# nixie-tube-clock_tube.net
KiCad netlist of a schematic drawn in EAGLE
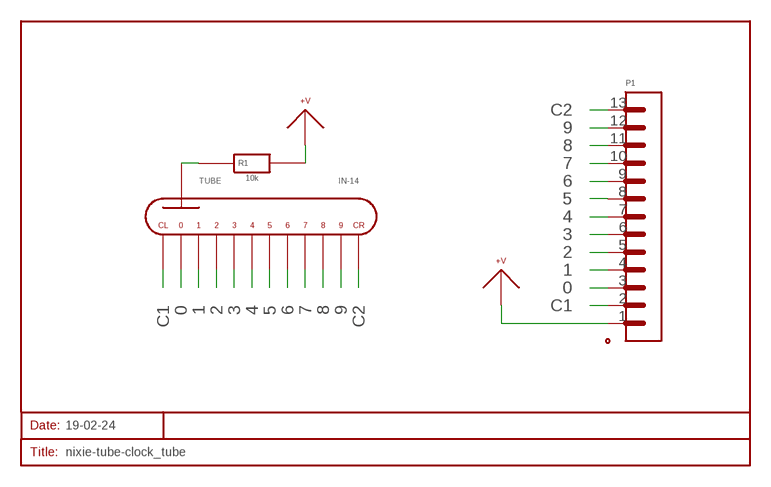
[diagram p0: schematic, sheet 1]

(export (version "E")
  (design (tool "Eeschema 10.0.6"))
  (components
    (comp (ref "P1")
      (value "PORT_13-PIN_HEADER")
      (footprint "eagle-import:HEADER_13-PIN")
      (libsource (lib "eagle-import") (part "PORT_13-PIN_HEADER"))
    )
    (comp (ref "R1")
      (value "10k")
      (footprint "eagle-import:RESISTOR_10.16MM")
      (libsource (lib "eagle-import") (part "RESISTOR"))
    )
    (comp (ref "SCHEMATIC1")
      (value "19-02-24")
      (footprint "eagle-import:SHEET")
      (libsource (lib "eagle-import") (part "SHEET"))
    )
    (comp (ref "TUBE")
      (value "IN-14")
      (footprint "eagle-import:NIXIE-TUBE_IN-14")
      (libsource (lib "eagle-import") (part "NIXIE-TUBE_IN-14_TUBE"))
    )
  )
  (nets
    (net (code "1") (name "+V") (class "Default")
      (node (ref "P1") (pin "1") (pinfunction "1_1") (pintype "bidirectional"))
      (node (ref "R1") (pin "2") (pinfunction "2_2") (pintype "bidirectional"))
    )
    (net (code "2") (name "/0") (class "Default")
      (node (ref "P1") (pin "3") (pinfunction "3_3") (pintype "bidirectional"))
      (node (ref "TUBE") (pin "0") (pinfunction "0_0") (pintype "bidirectional"))
    )
    (net (code "3") (name "/1") (class "Default")
      (node (ref "P1") (pin "4") (pinfunction "4_4") (pintype "bidirectional"))
      (node (ref "TUBE") (pin "1") (pinfunction "1_1") (pintype "bidirectional"))
    )
    (net (code "4") (name "/2") (class "Default")
      (node (ref "P1") (pin "5") (pinfunction "5_5") (pintype "bidirectional"))
      (node (ref "TUBE") (pin "2") (pinfunction "2_2") (pintype "bidirectional"))
    )
    (net (code "5") (name "/3") (class "Default")
      (node (ref "P1") (pin "6") (pinfunction "6_6") (pintype "bidirectional"))
      (node (ref "TUBE") (pin "3") (pinfunction "3_3") (pintype "bidirectional"))
    )
    (net (code "6") (name "/4") (class "Default")
      (node (ref "P1") (pin "7") (pinfunction "7_7") (pintype "bidirectional"))
      (node (ref "TUBE") (pin "4") (pinfunction "4_4") (pintype "bidirectional"))
    )
    (net (code "7") (name "/5") (class "Default")
      (node (ref "P1") (pin "8") (pinfunction "8_8") (pintype "bidirectional"))
      (node (ref "TUBE") (pin "5") (pinfunction "5_5") (pintype "bidirectional"))
    )
    (net (code "8") (name "/6") (class "Default")
      (node (ref "P1") (pin "9") (pinfunction "9_9") (pintype "bidirectional"))
      (node (ref "TUBE") (pin "6") (pinfunction "6_6") (pintype "bidirectional"))
    )
    (net (code "9") (name "/7") (class "Default")
      (node (ref "P1") (pin "10") (pinfunction "10_10") (pintype "bidirectional"))
      (node (ref "TUBE") (pin "7") (pinfunction "7_7") (pintype "bidirectional"))
    )
    (net (code "10") (name "/8") (class "Default")
      (node (ref "P1") (pin "11") (pinfunction "11_11") (pintype "bidirectional"))
      (node (ref "TUBE") (pin "8") (pinfunction "8_8") (pintype "bidirectional"))
    )
    (net (code "11") (name "/9") (class "Default")
      (node (ref "P1") (pin "12") (pinfunction "12_12") (pintype "bidirectional"))
      (node (ref "TUBE") (pin "9") (pinfunction "9_9") (pintype "bidirectional"))
    )
    (net (code "12") (name "/C1") (class "Default")
      (node (ref "P1") (pin "2") (pinfunction "2_2") (pintype "bidirectional"))
      (node (ref "TUBE") (pin "C1") (pinfunction "C1_C1") (pintype "bidirectional"))
    )
    (net (code "13") (name "/C2") (class "Default")
      (node (ref "P1") (pin "13") (pinfunction "13_13") (pintype "bidirectional"))
      (node (ref "TUBE") (pin "C2") (pinfunction "C2_C2") (pintype "bidirectional"))
    )
    (net (code "14") (name "Net-(TUBE-ANODE)") (class "Default")
      (node (ref "R1") (pin "1") (pinfunction "1_1") (pintype "bidirectional"))
      (node (ref "TUBE") (pin "A") (pinfunction "ANODE_A") (pintype "bidirectional"))
    )
  )
)
